# 11_-MAIN_POWER2.net
KiCad netlist of a schematic drawn in Altium Designer
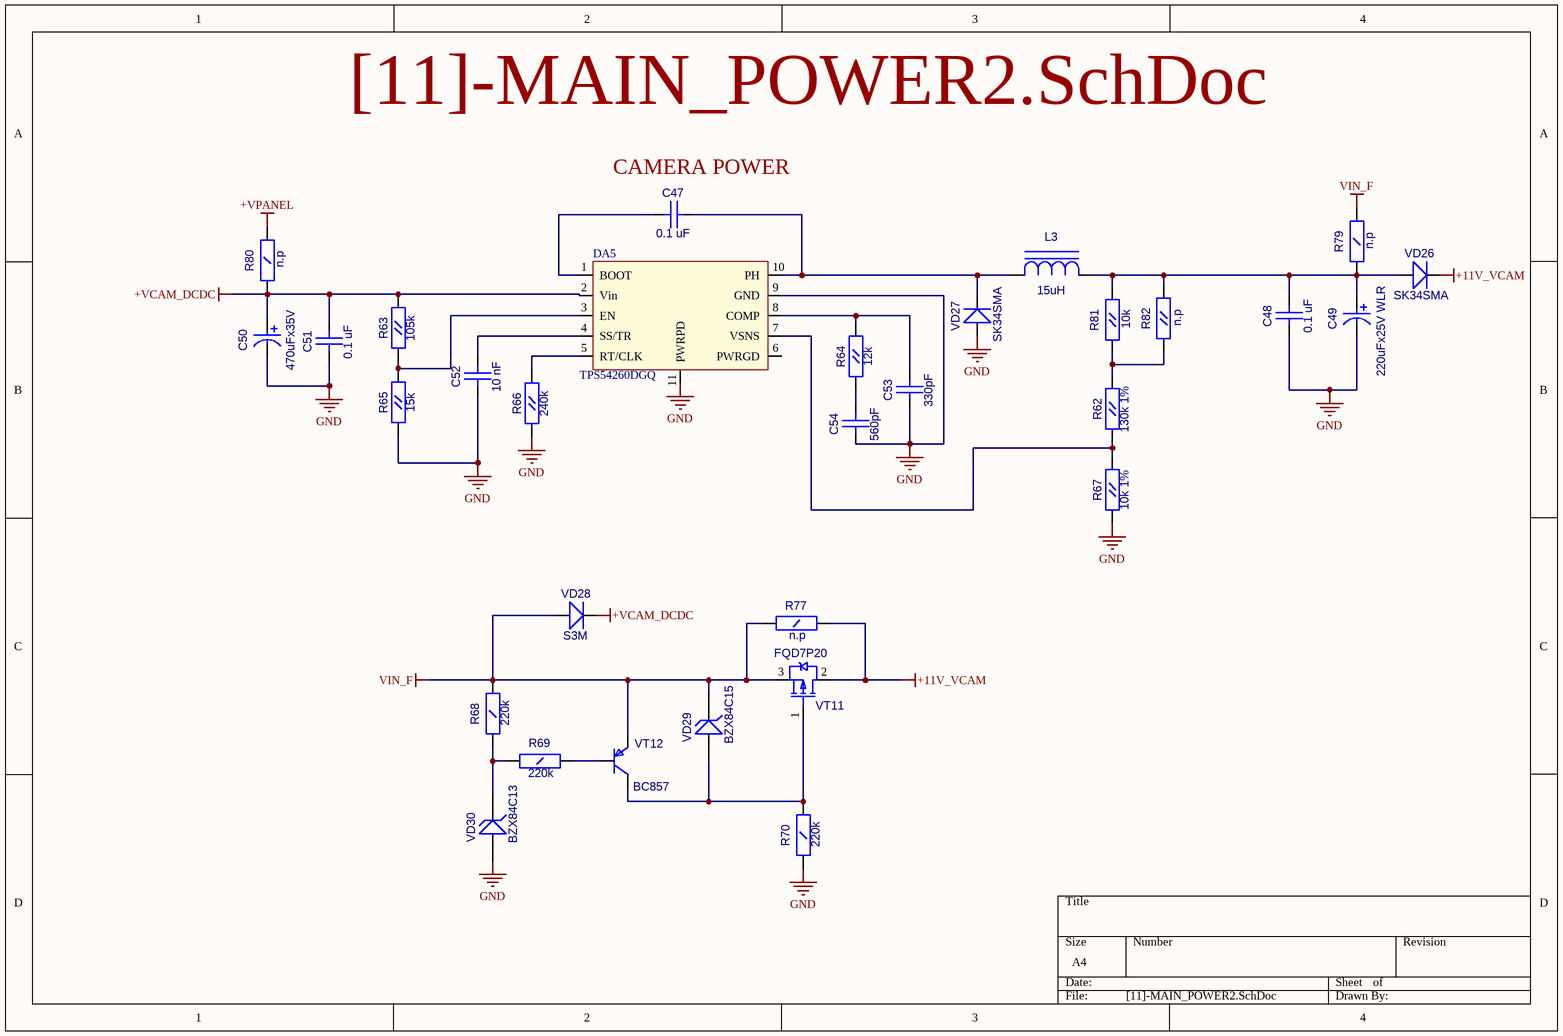
[diagram p0: [11]-MAIN_POWER2.SchDoc]

(export (version "E")
  (design (tool "Eeschema 10.0.6"))
  (components
    (comp (ref "C47")
      (value "0.1 uF")
      (footprint "CC0603")
      (description "CC0603")
      (libsource (lib "gprs_modem_2") (part "CC0603"))
    )
    (comp (ref "C48")
      (value "0.1 uF")
      (footprint "CC0603")
      (description "CC0603")
      (libsource (lib "gprs_modem_2") (part "CC0603"))
    )
    (comp (ref "C49")
      (value "220uFx25V WLR")
      (footprint "CC8X3.5")
      (description "CAP0.35")
      (libsource (lib "gprs_modem_2") (part "CAP0.35"))
    )
    (comp (ref "C50")
      (value "470uFx35V")
      (footprint "CC16X10_CAP0.5(1)(Primary)")
      (description "CAP0.5(1)")
      (libsource (lib "gprs_modem_2") (part "CAP0.5(1)"))
    )
    (comp (ref "C51")
      (value "0.1 uF")
      (footprint "CC0603")
      (description "CC0603")
      (libsource (lib "gprs_modem_2") (part "CC0603"))
    )
    (comp (ref "C52")
      (value "10 nF")
      (footprint "CC0603")
      (description "CC0603")
      (libsource (lib "gprs_modem_2") (part "CC0603"))
    )
    (comp (ref "C53")
      (value "330pF")
      (footprint "CC0603")
      (description "CC0603")
      (libsource (lib "gprs_modem_2") (part "CC0603"))
    )
    (comp (ref "C54")
      (value "560pF")
      (footprint "CC0603")
      (description "CC0603")
      (libsource (lib "gprs_modem_2") (part "CC0603"))
    )
    (comp (ref "DA5")
      (value "TPS54260DGQ")
      (footprint "S-PDSO-G10")
      (libsource (lib "gprs_modem_2") (part "TPS54260DGQ"))
    )
    (comp (ref "L3")
      (value "15uH")
      (footprint "SDR0805")
      (description "SDR0805")
      (libsource (lib "gprs_modem_2") (part "SDR0805"))
    )
    (comp (ref "R62")
      (value "130k 1%")
      (footprint "RC0603")
      (description "RC0603")
      (libsource (lib "gprs_modem_2") (part "RC0603"))
    )
    (comp (ref "R63")
      (value "105k")
      (footprint "RC0603")
      (description "RC0603")
      (libsource (lib "gprs_modem_2") (part "RC0603"))
    )
    (comp (ref "R64")
      (value "12k")
      (footprint "RC0603")
      (description "RC0603")
      (libsource (lib "gprs_modem_2") (part "RC0603"))
    )
    (comp (ref "R65")
      (value "15k")
      (footprint "RC0603")
      (description "RC0603")
      (libsource (lib "gprs_modem_2") (part "RC0603"))
    )
    (comp (ref "R66")
      (value "240k")
      (footprint "RC0603")
      (description "RC0603")
      (libsource (lib "gprs_modem_2") (part "RC0603"))
    )
    (comp (ref "R67")
      (value "10k 1%")
      (footprint "RC0603")
      (description "RC0603")
      (libsource (lib "gprs_modem_2") (part "RC0603"))
    )
    (comp (ref "R68")
      (value "220k")
      (footprint "RC1206")
      (description "RC1206")
      (libsource (lib "fizik_lib") (part "RC1206"))
    )
    (comp (ref "R69")
      (value "220k")
      (footprint "RC1206")
      (description "RC1206")
      (libsource (lib "fizik_lib") (part "RC1206"))
    )
    (comp (ref "R70")
      (value "220k")
      (footprint "RC1206")
      (description "RC1206")
      (libsource (lib "fizik_lib") (part "RC1206"))
    )
    (comp (ref "R77")
      (value "n.p")
      (footprint "RC1206")
      (description "RC1206")
      (libsource (lib "fizik_lib") (part "RC1206"))
    )
    (comp (ref "R79")
      (value "n.p")
      (footprint "RC1206")
      (description "RC1206")
      (libsource (lib "fizik_lib") (part "RC1206"))
    )
    (comp (ref "R80")
      (value "n.p")
      (footprint "RC1206")
      (description "RC1206")
      (libsource (lib "fizik_lib") (part "RC1206"))
    )
    (comp (ref "R81")
      (value "10k")
      (footprint "RC0603")
      (description "RC0603")
      (libsource (lib "fizik_lib") (part "RC0603"))
    )
    (comp (ref "R82")
      (value "n.p")
      (footprint "RC0603")
      (description "RC0603")
      (libsource (lib "fizik_lib") (part "RC0603"))
    )
    (comp (ref "VD26")
      (value "SK34SMA")
      (footprint "SMA")
      (description "Schottky Rectifier")
      (libsource (lib "gprs_modem") (part "SK34SMA"))
    )
    (comp (ref "VD27")
      (value "SK34SMA")
      (footprint "SMA")
      (description "Schottky Rectifier")
      (libsource (lib "gprs_modem") (part "SK34SMA"))
    )
    (comp (ref "VD28")
      (value "S3M")
      (footprint "SMC")
      (description "Schottky Rectifier")
      (libsource (lib "fizik_lib") (part "S3A"))
    )
    (comp (ref "VD29")
      (value "BZX84C15")
      (footprint "SOT-23(123)")
      (description "Zener Voltage Regulator Diode")
      (libsource (lib "fizik_lib") (part "BZX84"))
    )
    (comp (ref "VD30")
      (value "BZX84C13")
      (footprint "SOT-23(123)")
      (description "Zener Voltage Regulator Diode")
      (libsource (lib "fizik_lib") (part "BZX84"))
    )
    (comp (ref "VT11")
      (value "FQD7P20")
      (footprint "D-PAK(TO-252AA)")
      (description "HEXFET Power MOSFET")
      (libsource (lib "gprs_modem_2") (part "IRFR9220"))
    )
    (comp (ref "VT12")
      (value "BC857")
      (footprint "SOT-23(123)")
      (description "PNP 100ma transistor")
      (libsource (lib "gprs_modem_2") (part "BC857B"))
    )
  )
  (nets
    (net (code "1") (name "+11V_VCAM") (class "Default")
      (node (ref "R77") (pin "2") (pinfunction "B_2") (pintype "passive"))
      (node (ref "VD26") (pin "2") (pinfunction "K_2") (pintype "passive"))
      (node (ref "VT11") (pin "2") (pinfunction "D_2") (pintype "passive"))
    )
    (net (code "2") (name "+VCAM_DCDC") (class "Default")
      (node (ref "C50") (pin "2") (pintype "passive"))
      (node (ref "C51") (pin "1") (pinfunction "A_1") (pintype "passive"))
      (node (ref "DA5") (pin "2") (pinfunction "Vin_2") (pintype "passive"))
      (node (ref "R63") (pin "2") (pinfunction "B_2") (pintype "passive"))
      (node (ref "R80") (pin "1") (pinfunction "A_1") (pintype "passive"))
      (node (ref "VD28") (pin "2") (pinfunction "K_2") (pintype "passive"))
    )
    (net (code "3") (name "+VPANEL") (class "Default")
      (node (ref "R80") (pin "2") (pinfunction "B_2") (pintype "passive"))
    )
    (net (code "4") (name "GND") (class "Default")
      (node (ref "C48") (pin "2") (pinfunction "B_2") (pintype "passive"))
      (node (ref "C49") (pin "2") (pintype "passive"))
      (node (ref "C50") (pin "1") (pintype "passive"))
      (node (ref "C51") (pin "2") (pinfunction "B_2") (pintype "passive"))
      (node (ref "C52") (pin "2") (pinfunction "B_2") (pintype "passive"))
      (node (ref "C53") (pin "2") (pinfunction "B_2") (pintype "passive"))
      (node (ref "C54") (pin "2") (pinfunction "B_2") (pintype "passive"))
      (node (ref "DA5") (pin "11") (pinfunction "PWRPD_11") (pintype "passive"))
      (node (ref "DA5") (pin "9") (pinfunction "GND_9") (pintype "passive"))
      (node (ref "R65") (pin "1") (pinfunction "A_1") (pintype "passive"))
      (node (ref "R66") (pin "1") (pinfunction "A_1") (pintype "passive"))
      (node (ref "R67") (pin "1") (pinfunction "A_1") (pintype "passive"))
      (node (ref "R70") (pin "1") (pinfunction "A_1") (pintype "passive"))
      (node (ref "VD27") (pin "1") (pinfunction "A_1") (pintype "passive"))
      (node (ref "VD30") (pin "1") (pinfunction "A_1") (pintype "passive"))
    )
    (net (code "5") (name "Net-(C47-A)") (class "Default")
      (node (ref "C47") (pin "1") (pinfunction "A_1") (pintype "passive"))
      (node (ref "DA5") (pin "10") (pinfunction "PH_10") (pintype "passive"))
      (node (ref "L3") (pin "1") (pinfunction "C_1") (pintype "passive"))
      (node (ref "VD27") (pin "2") (pinfunction "K_2") (pintype "passive"))
    )
    (net (code "6") (name "Net-(C47-B)") (class "Default")
      (node (ref "C47") (pin "2") (pinfunction "B_2") (pintype "passive"))
      (node (ref "DA5") (pin "1") (pinfunction "BOOT_1") (pintype "passive"))
    )
    (net (code "7") (name "Net-(C48-A)") (class "Default")
      (node (ref "C48") (pin "1") (pinfunction "A_1") (pintype "passive"))
      (node (ref "C49") (pin "1") (pintype "passive"))
      (node (ref "L3") (pin "2") (pinfunction "A_2") (pintype "passive"))
      (node (ref "R79") (pin "1") (pinfunction "A_1") (pintype "passive"))
      (node (ref "R81") (pin "2") (pinfunction "B_2") (pintype "passive"))
      (node (ref "R82") (pin "2") (pinfunction "B_2") (pintype "passive"))
      (node (ref "VD26") (pin "1") (pinfunction "A_1") (pintype "passive"))
    )
    (net (code "8") (name "Net-(C52-A)") (class "Default")
      (node (ref "C52") (pin "1") (pinfunction "A_1") (pintype "passive"))
      (node (ref "DA5") (pin "4") (pinfunction "SS/TR_4") (pintype "passive"))
    )
    (net (code "9") (name "Net-(C53-A)") (class "Default")
      (node (ref "C53") (pin "1") (pinfunction "A_1") (pintype "passive"))
      (node (ref "DA5") (pin "8") (pinfunction "COMP_8") (pintype "passive"))
      (node (ref "R64") (pin "2") (pinfunction "B_2") (pintype "passive"))
    )
    (net (code "10") (name "Net-(C54-A)") (class "Default")
      (node (ref "C54") (pin "1") (pinfunction "A_1") (pintype "passive"))
      (node (ref "R64") (pin "1") (pinfunction "A_1") (pintype "passive"))
    )
    (net (code "11") (name "Net-(DA5-EN)") (class "Default")
      (node (ref "DA5") (pin "3") (pinfunction "EN_3") (pintype "passive"))
      (node (ref "R63") (pin "1") (pinfunction "A_1") (pintype "passive"))
      (node (ref "R65") (pin "2") (pinfunction "B_2") (pintype "passive"))
    )
    (net (code "12") (name "Net-(DA5-RT{slash}CLK)") (class "Default")
      (node (ref "DA5") (pin "5") (pinfunction "RT/CLK_5") (pintype "passive"))
      (node (ref "R66") (pin "2") (pinfunction "B_2") (pintype "passive"))
    )
    (net (code "13") (name "Net-(DA5-VSNS)") (class "Default")
      (node (ref "DA5") (pin "7") (pinfunction "VSNS_7") (pintype "passive"))
      (node (ref "R62") (pin "1") (pinfunction "A_1") (pintype "passive"))
      (node (ref "R67") (pin "2") (pinfunction "B_2") (pintype "passive"))
    )
    (net (code "14") (name "Net-(R62-B)") (class "Default")
      (node (ref "R62") (pin "2") (pinfunction "B_2") (pintype "passive"))
      (node (ref "R81") (pin "1") (pinfunction "A_1") (pintype "passive"))
      (node (ref "R82") (pin "1") (pinfunction "A_1") (pintype "passive"))
    )
    (net (code "15") (name "Net-(R68-A)") (class "Default")
      (node (ref "R68") (pin "1") (pinfunction "A_1") (pintype "passive"))
      (node (ref "R69") (pin "1") (pinfunction "A_1") (pintype "passive"))
      (node (ref "VD30") (pin "3") (pinfunction "K_3") (pintype "passive"))
    )
    (net (code "16") (name "Net-(R69-B)") (class "Default")
      (node (ref "R69") (pin "2") (pinfunction "B_2") (pintype "passive"))
      (node (ref "VT12") (pin "1") (pinfunction "B_1") (pintype "passive"))
    )
    (net (code "17") (name "Net-(R70-B)") (class "Default")
      (node (ref "R70") (pin "2") (pinfunction "B_2") (pintype "passive"))
      (node (ref "VD29") (pin "1") (pinfunction "A_1") (pintype "passive"))
      (node (ref "VT11") (pin "1") (pinfunction "G_1") (pintype "passive"))
      (node (ref "VT12") (pin "3") (pinfunction "C_3") (pintype "passive"))
    )
    (net (code "18") (name "VIN_F") (class "Default")
      (node (ref "R68") (pin "2") (pinfunction "B_2") (pintype "passive"))
      (node (ref "R77") (pin "1") (pinfunction "A_1") (pintype "passive"))
      (node (ref "R79") (pin "2") (pinfunction "B_2") (pintype "passive"))
      (node (ref "VD28") (pin "1") (pinfunction "A_1") (pintype "passive"))
      (node (ref "VD29") (pin "3") (pinfunction "K_3") (pintype "passive"))
      (node (ref "VT11") (pin "3") (pinfunction "S_3") (pintype "passive"))
      (node (ref "VT12") (pin "2") (pinfunction "E_2") (pintype "passive"))
    )
    (net (code "19") (name "unconnected-(DA5-PWRGD-Pad6)") (class "Default")
      (node (ref "DA5") (pin "6") (pinfunction "PWRGD_6") (pintype "passive"))
    )
  )
)
